# LM74670_ideal_diode_breakout.net
KiCad netlist of a schematic drawn in EAGLE
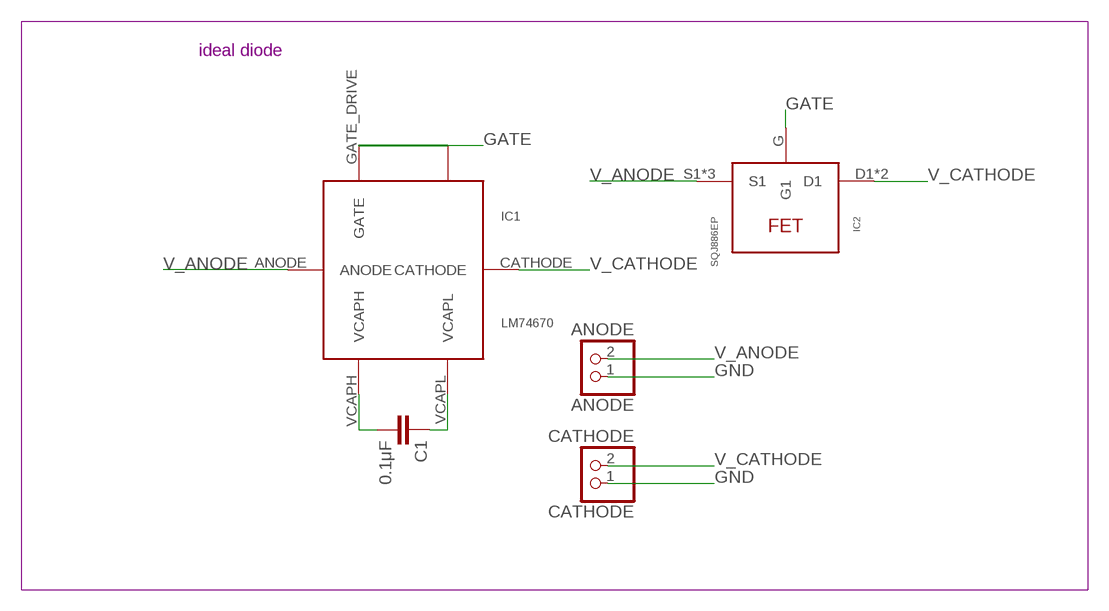
[diagram p0: schematic, sheet 1]

(export (version "E")
  (design (tool "Eeschema 10.0.6"))
  (components
    (comp (ref "ANODE")
      (value "ANODE")
      (footprint "eagle-import:1X02")
      (libsource (lib "eagle-import") (part "PINHD-1X2"))
    )
    (comp (ref "C1")
      (value "0.1μF")
      (footprint "eagle-import:C0805")
      (libsource (lib "eagle-import") (part "C-EUC0805"))
    )
    (comp (ref "CATHODE")
      (value "CATHODE")
      (footprint "eagle-import:1X02")
      (libsource (lib "eagle-import") (part "PINHD-1X2"))
    )
    (comp (ref "IC1")
      (value "LM74670")
      (footprint "eagle-import:VSSOP-8")
      (libsource (lib "eagle-import") (part "LM74670"))
    )
    (comp (ref "IC2")
      (value "SQJ886EP")
      (footprint "eagle-import:SO-8L")
      (libsource (lib "eagle-import") (part "SQJ886EP"))
    )
  )
  (nets
    (net (code "1") (name "/GATE") (class "Default")
      (node (ref "IC1") (pin "GATE_PULLD") (pinfunction "GATE_PULLD_GATE_PULLD") (pintype "bidirectional"))
      (node (ref "IC2") (pin "G") (pinfunction "G1_G") (pintype "bidirectional"))
    )
    (net (code "2") (name "/GND") (class "Default")
      (node (ref "ANODE") (pin "1") (pinfunction "1_1") (pintype "passive"))
      (node (ref "CATHODE") (pin "1") (pinfunction "1_1") (pintype "passive"))
    )
    (net (code "3") (name "/V_ANODE") (class "Default")
      (node (ref "ANODE") (pin "2") (pinfunction "2_2") (pintype "passive"))
      (node (ref "IC1") (pin "ANODE") (pinfunction "ANODE_ANODE") (pintype "bidirectional"))
      (node (ref "IC2") (pin "S1") (pinfunction "S1_S1") (pintype "bidirectional"))
      (node (ref "IC2") (pin "S2") (pinfunction "S1_S2") (pintype "bidirectional"))
      (node (ref "IC2") (pin "S3") (pinfunction "S1_S3") (pintype "bidirectional"))
    )
    (net (code "4") (name "/V_CATHODE") (class "Default")
      (node (ref "CATHODE") (pin "2") (pinfunction "2_2") (pintype "passive"))
      (node (ref "IC1") (pin "CATHODE") (pinfunction "CATHODE_CATHODE") (pintype "bidirectional"))
      (node (ref "IC2") (pin "D1") (pinfunction "D1_D1") (pintype "bidirectional"))
      (node (ref "IC2") (pin "D2") (pinfunction "D1_D2") (pintype "bidirectional"))
    )
    (net (code "5") (name "Net-(C1-Pad1)") (class "Default")
      (node (ref "C1") (pin "1") (pinfunction "1_1") (pintype "passive"))
      (node (ref "IC1") (pin "VCAPL") (pinfunction "VCAPL_VCAPL") (pintype "bidirectional"))
    )
    (net (code "6") (name "Net-(C1-Pad2)") (class "Default")
      (node (ref "C1") (pin "2") (pinfunction "2_2") (pintype "passive"))
      (node (ref "IC1") (pin "VCAPH") (pinfunction "VCAPH_VCAPH") (pintype "bidirectional"))
    )
    (net (code "7") (name "unconnected-(IC1-GATE-PadGATE_DRIVE)") (class "Default")
      (node (ref "IC1") (pin "GATE_DRIVE") (pinfunction "GATE_GATE_DRIVE") (pintype "bidirectional"))
    )
  )
)
